# PCB-Schematic-General-Sheet.net
KiCad netlist of a schematic drawn in Altium Designer
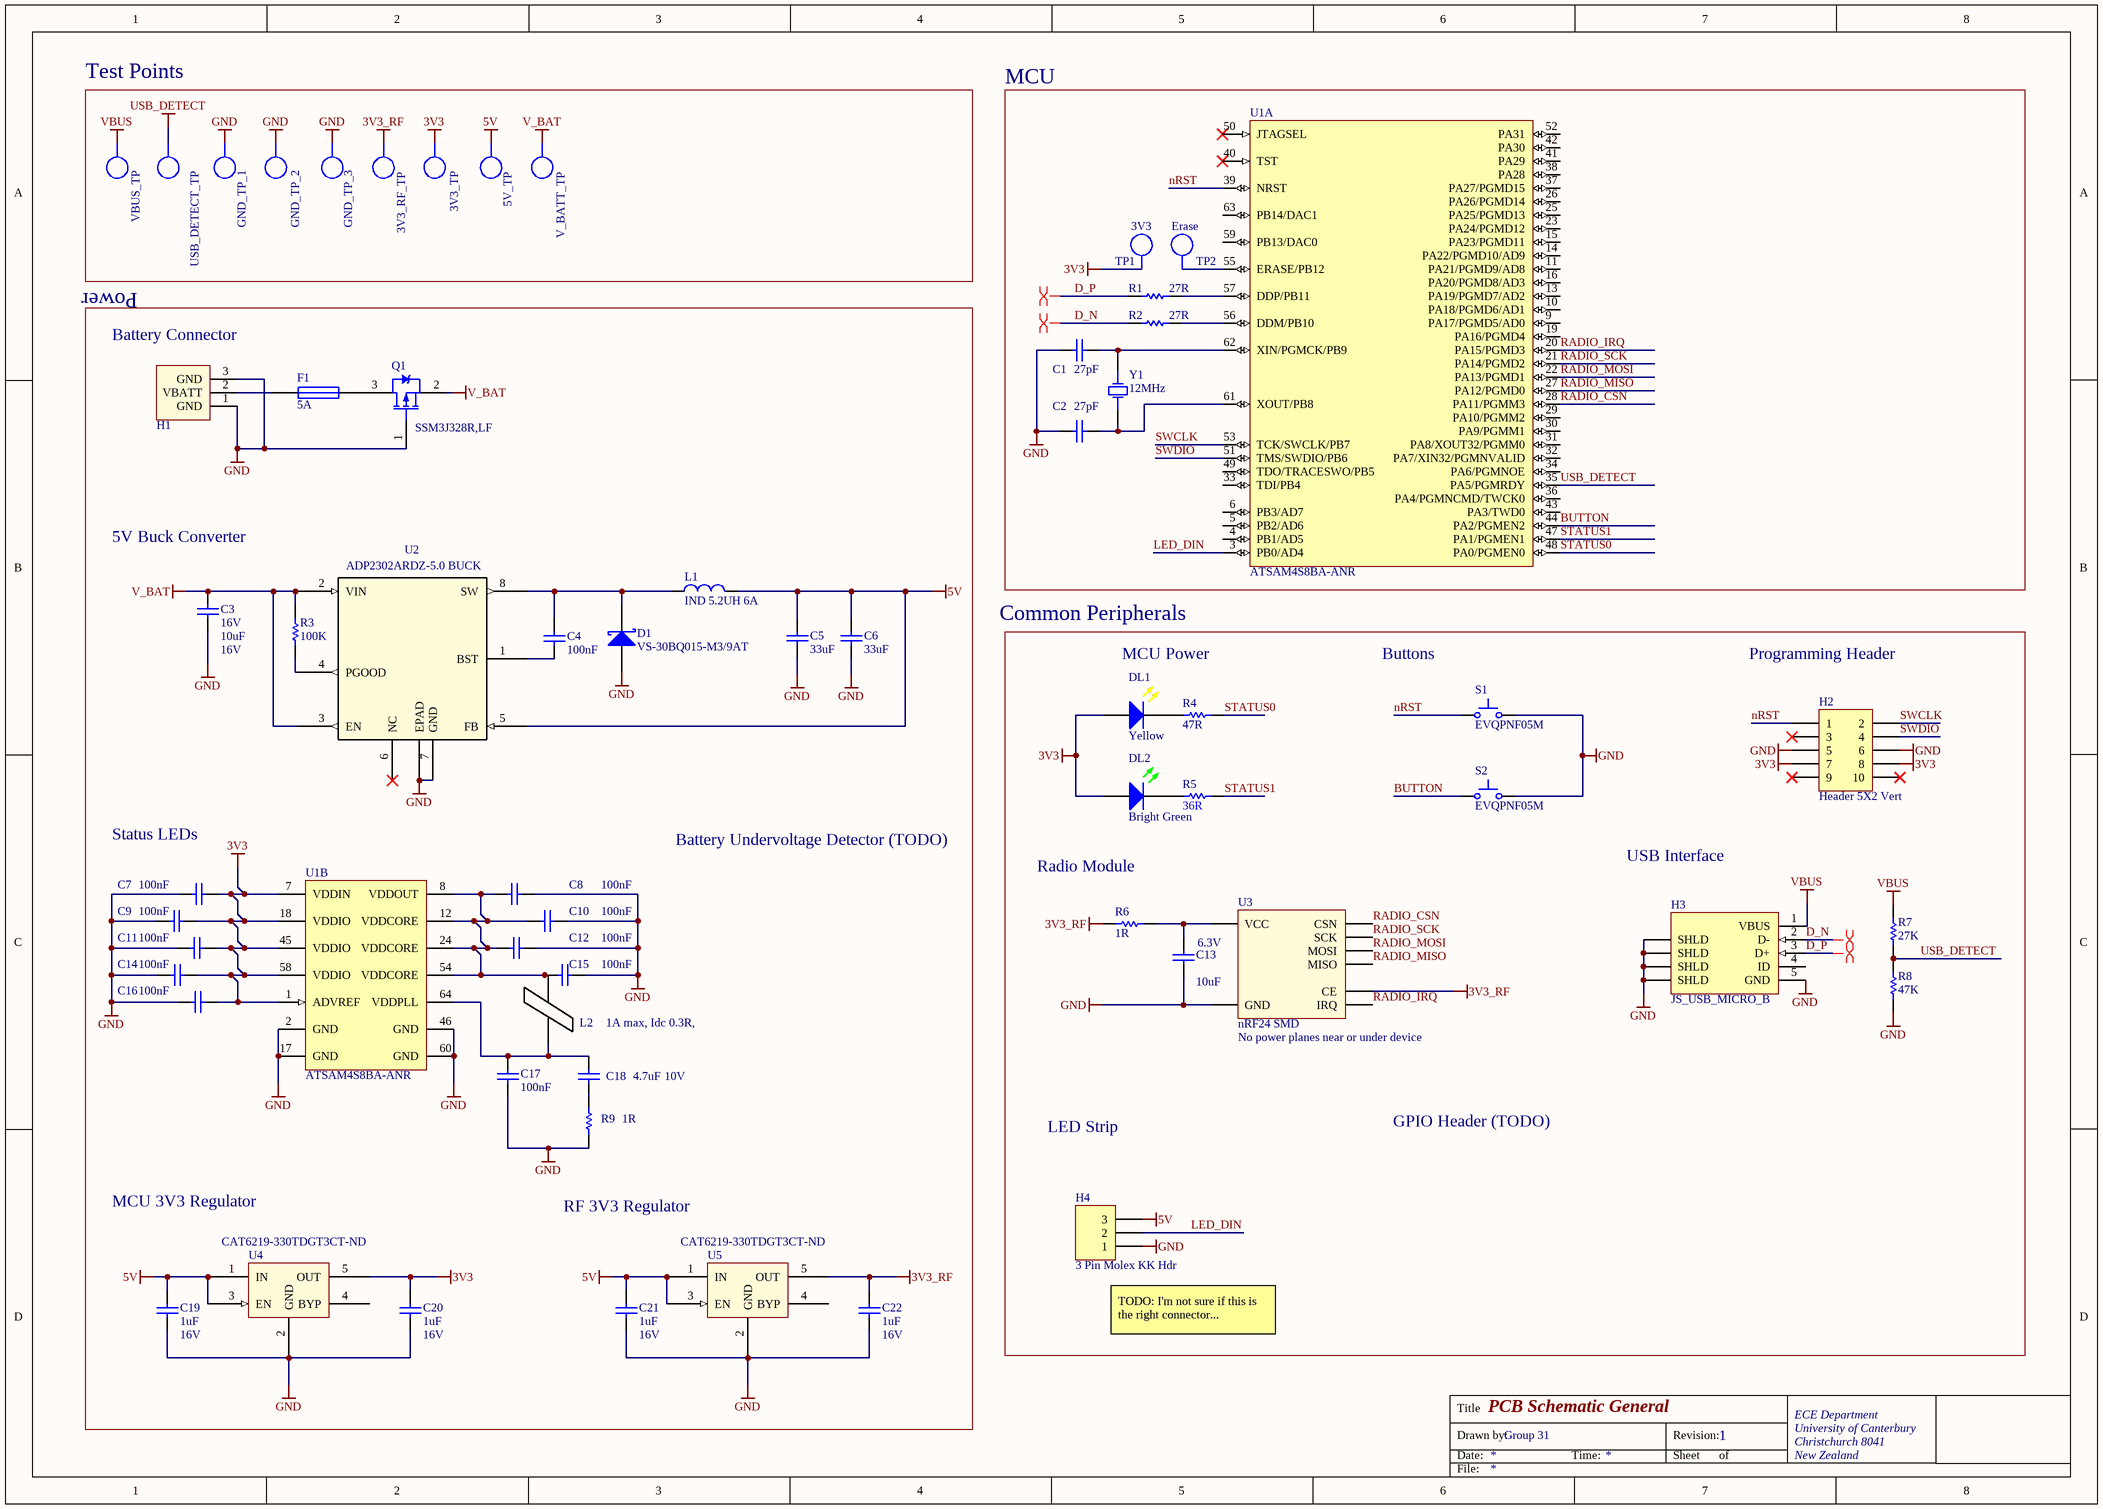
[diagram p0: PCB-Schematic-General-Sheet.schdoc]

(export (version "E")
  (design (tool "Eeschema 10.0.6"))
  (components
    (comp (ref "3V3_RF_TP")
      (value "TP")
      (footprint "TP_1206")
      (description "Test-Point 3.3x1.6x2.1mm SMD")
      (fields
        (field (name "MANUFACTURER") "Harwin Inc")
        (field (name "MANUFACTURER PART NUMBER") "S1751-46R")
      )
      (libsource (lib "ECE AD19Components_19V1") (part "TP_1206"))
    )
    (comp (ref "3V3_TP")
      (value "TP")
      (footprint "TP_1206")
      (description "Test-Point 3.3x1.6x2.1mm SMD")
      (fields
        (field (name "MANUFACTURER") "Harwin Inc")
        (field (name "MANUFACTURER PART NUMBER") "S1751-46R")
      )
      (libsource (lib "ECE AD19Components_19V1") (part "TP_1206"))
    )
    (comp (ref "5V_TP")
      (value "TP")
      (footprint "TP_1206")
      (description "Test-Point 3.3x1.6x2.1mm SMD")
      (fields
        (field (name "MANUFACTURER") "Harwin Inc")
        (field (name "MANUFACTURER PART NUMBER") "S1751-46R")
      )
      (libsource (lib "ECE AD19Components_19V1") (part "TP_1206"))
    )
    (comp (ref "C1")
      (value "27pF")
      (footprint "CAPC1608L")
      (description "CAP CER 27pF NPO/COG +-5% 50V 0603")
      (libsource (lib "ECE AD19Components_19V1") (part "CC_27pF_0603"))
    )
    (comp (ref "C2")
      (value "27pF")
      (footprint "CAPC1608L")
      (description "CAP CER 27pF NPO/COG +-5% 50V 0603")
      (libsource (lib "ECE AD19Components_19V1") (part "CC_27pF_0603"))
    )
    (comp (ref "C3")
      (value "10uF")
      (footprint "CAPC2012L")
      (description "CAP CER 10uF X5R 16V 0805")
      (fields
        (field (name "MANUFACTURER") "Samsung Electro-Mechanics")
        (field (name "MANUFACTURER PART NUMBER") "CL21A106KOQNNWE")
        (field (name "VOLTAGE - RATED") "16V")
        (field (name "MAX VOLTAGE") "16V")
      )
      (libsource (lib "ENCE461AD19_19V2") (part "CC_10uF_16V_0805"))
    )
    (comp (ref "C4")
      (value "100nF")
      (footprint "CAPC1608L")
      (description "CAP CER 100nF X7R +-10% 50V 0603")
      (libsource (lib "ECE AD19Components_19V1") (part "CC_100nF_0603"))
    )
    (comp (ref "C5")
      (value "33uF")
      (footprint "CAPC2012L")
      (description "CAP CER 33uF X5R 6V3 0805")
      (fields
        (field (name "MANUFACTURER") "TDK Corporation")
        (field (name "MANUFACTURER PART NUMBER") "C2012X5R0J336M125AC")
      )
      (libsource (lib "ENCE461AD19_19V2") (part "CC_33uF_6V3_0805"))
    )
    (comp (ref "C6")
      (value "33uF")
      (footprint "CAPC2012L")
      (description "CAP CER 33uF X5R 6V3 0805")
      (fields
        (field (name "MANUFACTURER") "TDK Corporation")
        (field (name "MANUFACTURER PART NUMBER") "C2012X5R0J336M125AC")
      )
      (libsource (lib "ENCE461AD19_19V2") (part "CC_33uF_6V3_0805"))
    )
    (comp (ref "C7")
      (value "100nF")
      (footprint "CAPC1608L")
      (description "CAP CER 100nF X7R +-10% 50V 0603")
      (libsource (lib "ECE AD19Components_19V1") (part "CC_100nF_0603"))
    )
    (comp (ref "C8")
      (value "100nF")
      (footprint "CAPC1608L")
      (description "CAP CER 100nF X7R +-10% 50V 0603")
      (libsource (lib "ECE AD19Components_19V1") (part "CC_100nF_0603"))
    )
    (comp (ref "C9")
      (value "100nF")
      (footprint "CAPC1608L")
      (description "CAP CER 100nF X7R +-10% 50V 0603")
      (libsource (lib "ECE AD19Components_19V1") (part "CC_100nF_0603"))
    )
    (comp (ref "C10")
      (value "100nF")
      (footprint "CAPC1608L")
      (description "CAP CER 100nF X7R +-10% 50V 0603")
      (libsource (lib "ECE AD19Components_19V1") (part "CC_100nF_0603"))
    )
    (comp (ref "C11")
      (value "100nF")
      (footprint "CAPC1608L")
      (description "CAP CER 100nF X7R +-10% 50V 0603")
      (libsource (lib "ECE AD19Components_19V1") (part "CC_100nF_0603"))
    )
    (comp (ref "C12")
      (value "100nF")
      (footprint "CAPC1608L")
      (description "CAP CER 100nF X7R +-10% 50V 0603")
      (libsource (lib "ECE AD19Components_19V1") (part "CC_100nF_0603"))
    )
    (comp (ref "C13")
      (value "10uF")
      (footprint "CAPC1608L")
      (description "CAP CER 10UF X5R +-20% 6V3 0603")
      (fields (field (name "VOLTAGE - RATED") "6.3V"))
      (libsource (lib "ECE AD19Components_19V1") (part "CC_10uF_0603"))
    )
    (comp (ref "C14")
      (value "100nF")
      (footprint "CAPC1608L")
      (description "CAP CER 100nF X7R +-10% 50V 0603")
      (libsource (lib "ECE AD19Components_19V1") (part "CC_100nF_0603"))
    )
    (comp (ref "C15")
      (value "100nF")
      (footprint "CAPC1608L")
      (description "CAP CER 100nF X7R +-10% 50V 0603")
      (libsource (lib "ECE AD19Components_19V1") (part "CC_100nF_0603"))
    )
    (comp (ref "C16")
      (value "100nF")
      (footprint "CAPC1608L")
      (description "CAP CER 100nF X7R +-10% 50V 0603")
      (libsource (lib "ECE AD19Components_19V1") (part "CC_100nF_0603"))
    )
    (comp (ref "C17")
      (value "100nF")
      (footprint "CAPC1608L")
      (description "CAP CER 100nF X7R +-10% 50V 0603")
      (libsource (lib "ECE AD19Components_19V1") (part "CC_100nF_0603"))
    )
    (comp (ref "C18")
      (value "4.7uF")
      (footprint "CAPC1608N")
      (description "CAP CER 4.7uF X5R +-20%  10V 0603")
      (fields (field (name "MAX VOLTAGE") "10V"))
      (libsource (lib "ECE AD19Components_19V1") (part "CC_4.7uF_0603"))
    )
    (comp (ref "C19")
      (value "1uF")
      (footprint "CAPC1608L")
      (description "CAP CER 1uF Y5V -20% +80% 16V 0603")
      (fields (field (name "MAX VOLTAGE") "16V"))
      (libsource (lib "ECE AD19Components_19V1") (part "CC_1uF_0603"))
    )
    (comp (ref "C20")
      (value "1uF")
      (footprint "CAPC1608L")
      (description "CAP CER 1uF Y5V -20% +80% 16V 0603")
      (fields (field (name "MAX VOLTAGE") "16V"))
      (libsource (lib "ECE AD19Components_19V1") (part "CC_1uF_0603"))
    )
    (comp (ref "C21")
      (value "1uF")
      (footprint "CAPC1608L")
      (description "CAP CER 1uF Y5V -20% +80% 16V 0603")
      (fields (field (name "MAX VOLTAGE") "16V"))
      (libsource (lib "ECE AD19Components_19V1") (part "CC_1uF_0603"))
    )
    (comp (ref "C22")
      (value "1uF")
      (footprint "CAPC1608L")
      (description "CAP CER 1uF Y5V -20% +80% 16V 0603")
      (fields (field (name "MAX VOLTAGE") "16V"))
      (libsource (lib "ECE AD19Components_19V1") (part "CC_1uF_0603"))
    )
    (comp (ref "D1")
      (value "VS-30BQ015-M3/9AT")
      (footprint "SMC")
      (description "DIODE, SCHOTTKY, 3A, 15V, DO-214AB / SMC")
      (fields (field (name "MANUFACTURER") "Vishay Semiconductors"))
      (libsource (lib "ECE AD19Components_19V1") (part "DS_VS-30BQ015-M3"))
    )
    (comp (ref "DL1")
      (value "Yellow")
      (footprint "WL-SMCW0603")
      (description "LED Yellow 120mcd 0603 SMD")
      (fields
        (field (name "MANUFACTURER") "WURTH ELEKTRONIK")
        (field (name "MANUFACTURER PART NUMBER") "150060YS75000")
        (field (name "LED COLOUR") "Yellow")
      )
      (libsource (lib "ECE AD19Components_19V1") (part "DL_150060YS75000"))
    )
    (comp (ref "DL2")
      (value "Bright Green")
      (footprint "WL-SMCW0603")
      (description "LED Bright Green 40mcd 0603 SMD")
      (fields
        (field (name "MANUFACTURER") "WURTH ELEKTRONIK")
        (field (name "MANUFACTURER PART NUMBER") "150060VS75000")
        (field (name "LED COLOUR") "Bright Green")
      )
      (libsource (lib "ECE AD19Components_19V1") (part "DL_150060VS75000"))
    )
    (comp (ref "F1")
      (value "5A")
      (footprint "RESC3216N")
      (description "Fuse 5.0A Fast Acting 1206 SMD")
      (fields (field (name "MANUFACTURER PART NUMBER") "C1F5") (field (name "MANUFACTURER") "Bel TRP"))
      (libsource (lib "ECE AD19Components_19V1") (part "FS_Fuse_5.0A"))
    )
    (comp (ref "GND_TP_1")
      (value "TP")
      (footprint "TP_1206")
      (description "Test-Point 3.3x1.6x2.1mm SMD")
      (fields
        (field (name "MANUFACTURER") "Harwin Inc")
        (field (name "MANUFACTURER PART NUMBER") "S1751-46R")
      )
      (libsource (lib "ECE AD19Components_19V1") (part "TP_1206"))
    )
    (comp (ref "GND_TP_2")
      (value "TP")
      (footprint "TP_1206")
      (description "Test-Point 3.3x1.6x2.1mm SMD")
      (fields
        (field (name "MANUFACTURER") "Harwin Inc")
        (field (name "MANUFACTURER PART NUMBER") "S1751-46R")
      )
      (libsource (lib "ECE AD19Components_19V1") (part "TP_1206"))
    )
    (comp (ref "GND_TP_3")
      (value "TP")
      (footprint "TP_1206")
      (description "Test-Point 3.3x1.6x2.1mm SMD")
      (fields
        (field (name "MANUFACTURER") "Harwin Inc")
        (field (name "MANUFACTURER PART NUMBER") "S1751-46R")
      )
      (libsource (lib "ECE AD19Components_19V1") (part "TP_1206"))
    )
    (comp (ref "H1")
      (value "Battery_HEADER_3pin")
      (footprint "BATT_HEADER_3POS")
      (description "3Pin Header 2.54mm spacing")
      (libsource (lib "ENCE461AD19_19V2") (part "Battery_HEADER_3pin"))
    )
    (comp (ref "H2")
      (value "Header 5X2 Vert")
      (footprint "IDC2.54-V10D")
      (description "IDC Header, 2,54mm, 10-Pin, Vert")
      (libsource (lib "ECE AD19Components_19V1") (part "JA_HDR_IDC_5X2_VERT"))
    )
    (comp (ref "H3")
      (value "JS_USB_MICRO_B")
      (footprint "FCI_USB_10118194-0001LF")
      (description "CONN USB MICRO B RECPT SMT R/A")
      (fields (field (name "MANUFACTURER") "FCI") (field (name "MANUFACTURER PART NUMBER") "10118194-0001LF"))
      (libsource (lib "ECE AD19Components_19V1") (part "JS_USB_MICRO_B_SMT"))
    )
    (comp (ref "H4")
      (value "3 Pin Molex KK Hdr")
      (footprint "MOLEX_KK_3_HDR")
      (description "CONN HEADER 3POS 2.54mm VERT_Thru Hole")
      (fields (field (name "MANUFACTURER") "Molex"))
      (libsource (lib "ECE AD19Components_19V1") (part "JA_MOLEX_KK_3POS"))
    )
    (comp (ref "L1")
      (value "IND 5.2UH 6A")
      (footprint "INDUCTOR5u2")
      (description "FIXED IND 5.2UH 6A 22 MOHM SMD")
      (fields
        (field (name "MANUFACTURER") "Sumida America Components Inc.")
        (field (name "MANUFACTURER PART NUMBER") "CDRH104RNP-5R2NC")
      )
      (libsource (lib "ENCE461AD19_19V2") (part "CDRH104RNP-5R2NC"))
    )
    (comp (ref "L2")
      (value "1A max, Idc 0.3R,")
      (footprint "INDC3216L")
      (description "Ferrite Bead, Rdc 0.3R, Z100MHZ 600R, Imax 1A, SMD 1206")
      (fields
        (field (name "MANUFACTURER") "FAIR-RITE")
        (field (name "MANUFACTURER PART NUMBER") "2512066017Y1")
      )
      (libsource (lib "ECE AD19Components_19V1") (part "IN_Ferrite-Bead"))
    )
    (comp (ref "Q1")
      (value "SSM3J328R,LF")
      (footprint "SOT23_L")
      (description "MOSFET P-CH 20V 6A SOT23-3")
      (fields
        (field (name "MANUFACTURER") "Toshiba")
        (field (name "MANUFACTURER PART NUMBER") "SSM3J328R,LF")
      )
      (libsource (lib "ECE AD19Components_19V1") (part "TM_SSM3J328R"))
    )
    (comp (ref "R1")
      (value "27R")
      (footprint "RESC1608L")
      (description "RES 27 OHM 1/10W 5% 0603 SMD")
      (libsource (lib "ECE AD19Components_19V1") (part "RS_27R"))
    )
    (comp (ref "R2")
      (value "27R")
      (footprint "RESC1608L")
      (description "RES 27 OHM 1/10W 5% 0603 SMD")
      (libsource (lib "ECE AD19Components_19V1") (part "RS_27R"))
    )
    (comp (ref "R3")
      (value "100K")
      (footprint "RESC1608L")
      (description "RES 100K OHM 1/10W 5% 0603 SMD")
      (libsource (lib "ECE AD19Components_19V1") (part "RS_100K"))
    )
    (comp (ref "R4")
      (value "47R")
      (footprint "RESC1608L")
      (description "RES 47 OHM 1/10W 5% 0603 SMD")
      (libsource (lib "ECE AD19Components_19V1") (part "RS_47R"))
    )
    (comp (ref "R5")
      (value "36R")
      (footprint "RESC1608L")
      (description "RES 36 OHM 1/10W 5% 0603 SMD")
      (libsource (lib "ECE AD19Components_19V1") (part "RS_36R"))
    )
    (comp (ref "R6")
      (value "1R")
      (footprint "RESC3216L")
      (description "RES 1R OHM 1/4W 5% 1206 SMD")
      (libsource (lib "ECE AD19Components_19V1") (part "RT_1R"))
    )
    (comp (ref "R7")
      (value "27K")
      (footprint "RESC1608L")
      (description "RES 27K OHM 1/10W 5% 0603 SMD")
      (libsource (lib "ECE AD19Components_19V1") (part "RS_27K"))
    )
    (comp (ref "R8")
      (value "47K")
      (footprint "RESC1608N")
      (description "RES 47.0K OHM 1/10W 5% 0603 SMD")
      (libsource (lib "ECE AD19Components_19V1") (part "RS_47K"))
    )
    (comp (ref "R9")
      (value "1R")
      (footprint "RESC3216L")
      (description "RES 1R OHM 1/4W 5% 1206 SMD")
      (libsource (lib "ECE AD19Components_19V1") (part "RT_1R"))
    )
    (comp (ref "S1")
      (value "EVQPNF05M")
      (footprint "EVQPNF05M")
      (description "Panasonic 6 x 3.5mm SMD Light Touch Switch Type SMD")
      (fields (field (name "MANUFACTURER") "Panasonic"))
      (libsource (lib "ECE AD19Components_19V1") (part "WS_EVQPNF05M"))
    )
    (comp (ref "S2")
      (value "EVQPNF05M")
      (footprint "EVQPNF05M")
      (description "Panasonic 6 x 3.5mm SMD Light Touch Switch Type SMD")
      (fields (field (name "MANUFACTURER") "Panasonic"))
      (libsource (lib "ECE AD19Components_19V1") (part "WS_EVQPNF05M"))
    )
    (comp (ref "TP1")
      (value "3V3")
      (footprint "TP_1206")
      (description "Test-Point 3.3x1.6x2.1mm SMD")
      (fields
        (field (name "MANUFACTURER") "Harwin Inc")
        (field (name "MANUFACTURER PART NUMBER") "S1751-46R")
      )
      (libsource (lib "ECE AD19Components_19V1") (part "TP_1206"))
    )
    (comp (ref "TP2")
      (value "Erase")
      (footprint "TP_1206")
      (description "Test-Point 3.3x1.6x2.1mm SMD")
      (fields
        (field (name "MANUFACTURER") "Harwin Inc")
        (field (name "MANUFACTURER PART NUMBER") "S1751-46R")
      )
      (libsource (lib "ECE AD19Components_19V1") (part "TP_1206"))
    )
    (comp (ref "U1")
      (value "ATSAM4S8BA-ANR")
      (footprint "LQFP64_L")
      (description "IC MCU 32BIT 512KB FLASH 64LQFP")
      (fields (field (name "MANUFACTURER") "Atmel"))
      (libsource (lib "ECE AD19Components_19V1") (part "SE_ATSAM4S16BA-MU"))
    )
    (comp (ref "U2")
      (value "ADP2302ARDZ-5.0 BUCK")
      (footprint "RD_8_1")
      (description "IC REG BUCK 5V 2A 8SOIC")
      (fields (field (name "MANUFACTURER_PART_NUMBER") "ADP2302ARDZ-5.0-R7"))
      (libsource (lib "ENCE461AD19_19V2") (part "ADP2302ARDZ-5.0-R7"))
    )
    (comp (ref "U3")
      (value "nRF24 SMD")
      (footprint "NRF24")
      (description "nRF24 SMD Module")
      (fields (field (name "WARNING") "No power planes near or under device"))
      (libsource (lib "ENCE461AD19_19V2") (part "NRF24"))
    )
    (comp (ref "U4")
      (value "CAT6219-330TDGT3")
      (footprint "SOT95P280X145-5N")
      (description "IC REG LIN 3.3V 500MA TSOT23-5")
      (fields
        (field (name "BASE PART NUMBER") "CAT6219")
        (field (name "SUPPLIER PART NUMBER") "CAT6219-330TDGT3CT-ND")
      )
      (libsource (lib "ENCE461AD19_19V2") (part "SV_CAT6219-330TDGT3"))
    )
    (comp (ref "U5")
      (value "CAT6219-330TDGT3")
      (footprint "SOT95P280X145-5N")
      (description "IC REG LIN 3.3V 500MA TSOT23-5")
      (fields
        (field (name "BASE PART NUMBER") "CAT6219")
        (field (name "SUPPLIER PART NUMBER") "CAT6219-330TDGT3CT-ND")
      )
      (libsource (lib "ENCE461AD19_19V2") (part "SV_CAT6219-330TDGT3"))
    )
    (comp (ref "USB_DETECT_TP")
      (value "TP")
      (footprint "TP_1206")
      (description "Test-Point 3.3x1.6x2.1mm SMD")
      (fields
        (field (name "MANUFACTURER") "Harwin Inc")
        (field (name "MANUFACTURER PART NUMBER") "S1751-46R")
      )
      (libsource (lib "ECE AD19Components_19V1") (part "TP_1206"))
    )
    (comp (ref "VBUS_TP")
      (value "TP")
      (footprint "TP_1206")
      (description "Test-Point 3.3x1.6x2.1mm SMD")
      (fields
        (field (name "MANUFACTURER") "Harwin Inc")
        (field (name "MANUFACTURER PART NUMBER") "S1751-46R")
      )
      (libsource (lib "ECE AD19Components_19V1") (part "TP_1206"))
    )
    (comp (ref "V_BATT_TP")
      (value "TP")
      (footprint "TP_1206")
      (description "Test-Point 3.3x1.6x2.1mm SMD")
      (fields
        (field (name "MANUFACTURER") "Harwin Inc")
        (field (name "MANUFACTURER PART NUMBER") "S1751-46R")
      )
      (libsource (lib "ECE AD19Components_19V1") (part "TP_1206"))
    )
    (comp (ref "Y1")
      (value "12MHz")
      (footprint "6.0X3.5-4")
      (description "CRYSTAL 12MHZ 18PF 6X3.5mm SMD")
      (fields
        (field (name "MANUFACTURER") "CTS-Frequency Controls")
        (field (name "MANUFACTURER PART NUMBER") "406C35D12M00000")
        (field (name "FREQUENCY") "12MHz")
      )
      (libsource (lib "ECE AD19Components_19V1") (part "XT_CRYSTAL_12MHz_18pF"))
    )
  )
  (nets
    (net (code "1") (name "/BUTTON") (class "Default")
      (node (ref "S2") (pin "1") (pintype "passive"))
      (node (ref "U1") (pin "44") (pinfunction "PA2/PGMEN2_44") (pintype "bidirectional"))
    )
    (net (code "2") (name "/D_N") (class "Default")
      (node (ref "H3") (pin "2") (pinfunction "D-_2") (pintype "input"))
      (node (ref "R2") (pin "1") (pinfunction "1_1") (pintype "passive"))
    )
    (net (code "3") (name "/D_P") (class "Default")
      (node (ref "H3") (pin "3") (pinfunction "D+_3") (pintype "input"))
      (node (ref "R1") (pin "1") (pinfunction "1_1") (pintype "passive"))
    )
    (net (code "4") (name "/LED_DIN") (class "Default")
      (node (ref "H4") (pin "2") (pinfunction "2_2") (pintype "passive"))
      (node (ref "U1") (pin "3") (pinfunction "PB0/AD4_3") (pintype "bidirectional"))
    )
    (net (code "5") (name "/RADIO_CSN") (class "Default")
      (node (ref "U1") (pin "28") (pinfunction "PA11/PGMM3_28") (pintype "bidirectional"))
      (node (ref "U3") (pin "4") (pinfunction "CSN_4") (pintype "passive"))
    )
    (net (code "6") (name "/RADIO_IRQ") (class "Default")
      (node (ref "U1") (pin "20") (pinfunction "PA15/PGMD3_20") (pintype "bidirectional"))
      (node (ref "U3") (pin "8") (pinfunction "IRQ_8") (pintype "passive"))
    )
    (net (code "7") (name "/RADIO_MISO") (class "Default")
      (node (ref "U1") (pin "27") (pinfunction "PA12/PGMD0_27") (pintype "bidirectional"))
      (node (ref "U3") (pin "7") (pinfunction "MISO_7") (pintype "passive"))
    )
    (net (code "8") (name "/RADIO_MOSI") (class "Default")
      (node (ref "U1") (pin "22") (pinfunction "PA13/PGMD1_22") (pintype "bidirectional"))
      (node (ref "U3") (pin "6") (pinfunction "MOSI_6") (pintype "passive"))
    )
    (net (code "9") (name "/RADIO_SCK") (class "Default")
      (node (ref "U1") (pin "21") (pinfunction "PA14/PGMD2_21") (pintype "bidirectional"))
      (node (ref "U3") (pin "5") (pinfunction "SCK_5") (pintype "passive"))
    )
    (net (code "10") (name "/STATUS0") (class "Default")
      (node (ref "R4") (pin "2") (pinfunction "2_2") (pintype "passive"))
      (node (ref "U1") (pin "48") (pinfunction "PA0/PGMEN0_48") (pintype "bidirectional"))
    )
    (net (code "11") (name "/STATUS1") (class "Default")
      (node (ref "R5") (pin "2") (pinfunction "2_2") (pintype "passive"))
      (node (ref "U1") (pin "47") (pinfunction "PA1/PGMEN1_47") (pintype "bidirectional"))
    )
    (net (code "12") (name "/SWCLK") (class "Default")
      (node (ref "H2") (pin "2") (pinfunction "2_2") (pintype "passive"))
      (node (ref "U1") (pin "53") (pinfunction "TCK/SWCLK/PB7_53") (pintype "bidirectional"))
    )
    (net (code "13") (name "/SWDIO") (class "Default")
      (node (ref "H2") (pin "4") (pinfunction "4_4") (pintype "passive"))
      (node (ref "U1") (pin "51") (pinfunction "TMS/SWDIO/PB6_51") (pintype "bidirectional"))
    )
    (net (code "14") (name "/nRST") (class "Default")
      (node (ref "H2") (pin "1") (pinfunction "1_1") (pintype "passive"))
      (node (ref "S1") (pin "1") (pintype "passive"))
      (node (ref "U1") (pin "39") (pinfunction "NRST_39") (pintype "bidirectional"))
    )
    (net (code "15") (name "3V3") (class "Default")
      (node (ref "3V3_TP") (pin "1") (pinfunction "1_1") (pintype "passive"))
      (node (ref "C11") (pin "2") (pinfunction "2_2") (pintype "passive"))
      (node (ref "C14") (pin "2") (pinfunction "2_2") (pintype "passive"))
      (node (ref "C16") (pin "2") (pinfunction "2_2") (pintype "passive"))
      (node (ref "C20") (pin "2") (pinfunction "2_2") (pintype "passive"))
      (node (ref "C7") (pin "2") (pinfunction "2_2") (pintype "passive"))
      (node (ref "C9") (pin "2") (pinfunction "2_2") (pintype "passive"))
      (node (ref "DL1") (pin "2") (pinfunction "A_2") (pintype "passive"))
      (node (ref "DL2") (pin "2") (pinfunction "A_2") (pintype "passive"))
      (node (ref "H2") (pin "7") (pinfunction "7_7") (pintype "passive"))
      (node (ref "H2") (pin "8") (pinfunction "8_8") (pintype "passive"))
      (node (ref "TP1") (pin "1") (pinfunction "1_1") (pintype "passive"))
      (node (ref "U1") (pin "1") (pinfunction "ADVREF_1") (pintype "input"))
      (node (ref "U1") (pin "18") (pinfunction "VDDIO_18") (pintype "power_in"))
      (node (ref "U1") (pin "45") (pinfunction "VDDIO_45") (pintype "power_in"))
      (node (ref "U1") (pin "58") (pinfunction "VDDIO_58") (pintype "power_in"))
      (node (ref "U1") (pin "7") (pinfunction "VDDIN_7") (pintype "power_in"))
      (node (ref "U4") (pin "5") (pinfunction "OUT_5") (pintype "power_in"))
    )
    (net (code "16") (name "3V3_RF") (class "Default")
      (node (ref "3V3_RF_TP") (pin "1") (pinfunction "1_1") (pintype "passive"))
      (node (ref "C22") (pin "2") (pinfunction "2_2") (pintype "passive"))
      (node (ref "R6") (pin "1") (pinfunction "1_1") (pintype "passive"))
      (node (ref "U3") (pin "3") (pinfunction "CE_3") (pintype "passive"))
      (node (ref "U5") (pin "5") (pinfunction "OUT_5") (pintype "power_in"))
    )
    (net (code "17") (name "5V") (class "Default")
      (node (ref "5V_TP") (pin "1") (pinfunction "1_1") (pintype "passive"))
      (node (ref "C19") (pin "2") (pinfunction "2_2") (pintype "passive"))
      (node (ref "C21") (pin "2") (pinfunction "2_2") (pintype "passive"))
      (node (ref "C5") (pin "2") (pinfunction "2_2") (pintype "passive"))
      (node (ref "C6") (pin "2") (pinfunction "2_2") (pintype "passive"))
      (node (ref "H4") (pin "3") (pinfunction "3_3") (pintype "passive"))
      (node (ref "L1") (pin "2") (pintype "passive"))
      (node (ref "U2") (pin "5") (pinfunction "FB_5") (pintype "input"))
      (node (ref "U4") (pin "1") (pinfunction "IN_1") (pintype "power_in"))
      (node (ref "U4") (pin "3") (pinfunction "EN_3") (pintype "input"))
      (node (ref "U5") (pin "1") (pinfunction "IN_1") (pintype "power_in"))
      (node (ref "U5") (pin "3") (pinfunction "EN_3") (pintype "input"))
    )
    (net (code "18") (name "GND") (class "Default")
      (node (ref "C1") (pin "1") (pinfunction "1_1") (pintype "passive"))
      (node (ref "C10") (pin "2") (pinfunction "2_2") (pintype "passive"))
      (node (ref "C11") (pin "1") (pinfunction "1_1") (pintype "passive"))
      (node (ref "C12") (pin "2") (pinfunction "2_2") (pintype "passive"))
      (node (ref "C13") (pin "1") (pinfunction "1_1") (pintype "passive"))
      (node (ref "C14") (pin "1") (pinfunction "1_1") (pintype "passive"))
      (node (ref "C15") (pin "2") (pinfunction "2_2") (pintype "passive"))
      (node (ref "C16") (pin "1") (pinfunction "1_1") (pintype "passive"))
      (node (ref "C17") (pin "1") (pinfunction "1_1") (pintype "passive"))
      (node (ref "C19") (pin "1") (pinfunction "1_1") (pintype "passive"))
      (node (ref "C2") (pin "1") (pinfunction "1_1") (pintype "passive"))
      (node (ref "C20") (pin "1") (pinfunction "1_1") (pintype "passive"))
      (node (ref "C21") (pin "1") (pinfunction "1_1") (pintype "passive"))
      (node (ref "C22") (pin "1") (pinfunction "1_1") (pintype "passive"))
      (node (ref "C3") (pin "1") (pinfunction "1_1") (pintype "passive"))
      (node (ref "C5") (pin "1") (pinfunction "1_1") (pintype "passive"))
      (node (ref "C6") (pin "1") (pinfunction "1_1") (pintype "passive"))
      (node (ref "C7") (pin "1") (pinfunction "1_1") (pintype "passive"))
      (node (ref "C8") (pin "2") (pinfunction "2_2") (pintype "passive"))
      (node (ref "C9") (pin "1") (pinfunction "1_1") (pintype "passive"))
      (node (ref "D1") (pin "1") (pinfunction "A_1") (pintype "passive"))
      (node (ref "GND_TP_1") (pin "1") (pinfunction "1_1") (pintype "passive"))
      (node (ref "GND_TP_2") (pin "1") (pinfunction "1_1") (pintype "passive"))
      (node (ref "GND_TP_3") (pin "1") (pinfunction "1_1") (pintype "passive"))
      (node (ref "H1") (pin "1") (pinfunction "GND_1") (pintype "passive"))
      (node (ref "H1") (pin "3") (pinfunction "GND_3") (pintype "passive"))
      (node (ref "H2") (pin "5") (pinfunction "5_5") (pintype "passive"))
      (node (ref "H2") (pin "6") (pinfunction "6_6") (pintype "passive"))
      (node (ref "H3") (pin "5") (pinfunction "GND_5") (pintype "passive"))
      (node (ref "H3") (pin "6") (pinfunction "SHLD_6") (pintype "passive"))
      (node (ref "H4") (pin "1") (pinfunction "1_1") (pintype "passive"))
      (node (ref "Q1") (pin "1") (pinfunction "1_1") (pintype "passive"))
      (node (ref "R8") (pin "1") (pinfunction "1_1") (pintype "passive"))
      (node (ref "R9") (pin "1") (pinfunction "1_1") (pintype "passive"))
      (node (ref "S1") (pin "2") (pintype "passive"))
      (node (ref "S2") (pin "2") (pintype "passive"))
      (node (ref "U1") (pin "17") (pinfunction "GND_17") (pintype "power_in"))
      (node (ref "U1") (pin "2") (pinfunction "GND_2") (pintype "power_in"))
      (node (ref "U1") (pin "46") (pinfunction "GND_46") (pintype "power_in"))
      (node (ref "U1") (pin "60") (pinfunction "GND_60") (pintype "power_in"))
      (node (ref "U2") (pin "7") (pinfunction "GND_7") (pintype "power_in"))
      (node (ref "U2") (pin "EPAD") (pinfunction "EPAD_EPAD") (pintype "passive"))
      (node (ref "U3") (pin "2") (pinfunction "GND_2") (pintype "passive"))
      (node (ref "U4") (pin "2") (pinfunction "GND_2") (pintype "power_in"))
      (node (ref "U5") (pin "2") (pinfunction "GND_2") (pintype "power_in"))
    )
    (net (code "19") (name "Net-(C18-Pad1)") (class "Default")
      (node (ref "C18") (pin "1") (pinfunction "1_1") (pintype "passive"))
      (node (ref "R9") (pin "2") (pinfunction "2_2") (pintype "passive"))
    )
    (net (code "20") (name "Net-(D1-K)") (class "Default")
      (node (ref "C4") (pin "2") (pinfunction "2_2") (pintype "passive"))
      (node (ref "D1") (pin "2") (pinfunction "K_2") (pintype "passive"))
      (node (ref "L1") (pin "1") (pintype "passive"))
      (node (ref "U2") (pin "8") (pinfunction "SW_8") (pintype "output"))
    )
    (net (code "21") (name "Net-(DL1-K)") (class "Default")
      (node (ref "DL1") (pin "1") (pinfunction "K_1") (pintype "passive"))
      (node (ref "R4") (pin "1") (pinfunction "1_1") (pintype "passive"))
    )
    (net (code "22") (name "Net-(DL2-K)") (class "Default")
      (node (ref "DL2") (pin "1") (pinfunction "K_1") (pintype "passive"))
      (node (ref "R5") (pin "1") (pinfunction "1_1") (pintype "passive"))
    )
    (net (code "23") (name "Net-(F1-Pad2)") (class "Default")
      (node (ref "F1") (pin "2") (pinfunction "2_2") (pintype "passive"))
      (node (ref "Q1") (pin "3") (pinfunction "3_3") (pintype "passive"))
    )
    (net (code "24") (name "Net-(H1-VBATT)") (class "Default")
      (node (ref "F1") (pin "1") (pinfunction "1_1") (pintype "passive"))
      (node (ref "H1") (pin "2") (pinfunction "VBATT_2") (pintype "passive"))
    )
    (net (code "25") (name "Net-(U1A-DDM{slash}PB10)") (class "Default")
      (node (ref "R2") (pin "2") (pinfunction "2_2") (pintype "passive"))
      (node (ref "U1") (pin "56") (pinfunction "DDM/PB10_56") (pintype "bidirectional"))
    )
    (net (code "26") (name "Net-(U1A-DDP{slash}PB11)") (class "Default")
      (node (ref "R1") (pin "2") (pinfunction "2_2") (pintype "passive"))
      (node (ref "U1") (pin "57") (pinfunction "DDP/PB11_57") (pintype "bidirectional"))
    )
    (net (code "27") (name "Net-(U1A-ERASE{slash}PB12)") (class "Default")
      (node (ref "TP2") (pin "1") (pinfunction "1_1") (pintype "passive"))
      (node (ref "U1") (pin "55") (pinfunction "ERASE/PB12_55") (pintype "bidirectional"))
    )
    (net (code "28") (name "Net-(U1A-XIN{slash}PGMCK{slash}PB9)") (class "Default")
      (node (ref "C1") (pin "2") (pinfunction "2_2") (pintype "passive"))
      (node (ref "U1") (pin "62") (pinfunction "XIN/PGMCK/PB9_62") (pintype "bidirectional"))
      (node (ref "Y1") (pin "1") (pinfunction "OSC1_1") (pintype "passive"))
    )
    (net (code "29") (name "Net-(U1A-XOUT{slash}PB8)") (class "Default")
      (node (ref "C2") (pin "2") (pinfunction "2_2") (pintype "passive"))
      (node (ref "U1") (pin "61") (pinfunction "XOUT/PB8_61") (pintype "bidirectional"))
      (node (ref "Y1") (pin "3") (pinfunction "OSC2_3") (pintype "passive"))
    )
    (net (code "30") (name "Net-(U1B-VDDOUT)") (class "Default")
      (node (ref "C10") (pin "1") (pinfunction "1_1") (pintype "passive"))
      (node (ref "C12") (pin "1") (pinfunction "1_1") (pintype "passive"))
      (node (ref "C15") (pin "1") (pinfunction "1_1") (pintype "passive"))
      (node (ref "C8") (pin "1") (pinfunction "1_1") (pintype "passive"))
      (node (ref "L2") (pin "2") (pinfunction "2_2") (pintype "passive"))
      (node (ref "U1") (pin "12") (pinfunction "VDDCORE_12") (pintype "power_in"))
      (node (ref "U1") (pin "24") (pinfunction "VDDCORE_24") (pintype "power_in"))
      (node (ref "U1") (pin "54") (pinfunction "VDDCORE_54") (pintype "power_in"))
      (node (ref "U1") (pin "8") (pinfunction "VDDOUT_8") (pintype "power_in"))
    )
    (net (code "31") (name "Net-(U1B-VDDPLL)") (class "Default")
      (node (ref "C17") (pin "2") (pinfunction "2_2") (pintype "passive"))
      (node (ref "C18") (pin "2") (pinfunction "2_2") (pintype "passive"))
      (node (ref "L2") (pin "1") (pinfunction "1_1") (pintype "passive"))
      (node (ref "U1") (pin "64") (pinfunction "VDDPLL_64") (pintype "power_in"))
    )
    (net (code "32") (name "Net-(U2-BST)") (class "Default")
      (node (ref "C4") (pin "1") (pinfunction "1_1") (pintype "passive"))
      (node (ref "U2") (pin "1") (pinfunction "BST_1") (pintype "passive"))
    )
    (net (code "33") (name "Net-(U2-PGOOD)") (class "Default")
      (node (ref "R3") (pin "1") (pinfunction "1_1") (pintype "passive"))
      (node (ref "U2") (pin "4") (pinfunction "PGOOD_4") (pintype "output"))
    )
    (net (code "34") (name "Net-(U3-VCC)") (class "Default")
      (node (ref "C13") (pin "2") (pinfunction "2_2") (pintype "passive"))
      (node (ref "R6") (pin "2") (pinfunction "2_2") (pintype "passive"))
      (node (ref "U3") (pin "1") (pinfunction "VCC_1") (pintype "passive"))
    )
    (net (code "35") (name "USB_DETECT") (class "Default")
      (node (ref "R7") (pin "1") (pinfunction "1_1") (pintype "passive"))
      (node (ref "R8") (pin "2") (pinfunction "2_2") (pintype "passive"))
      (node (ref "U1") (pin "35") (pinfunction "PA5/PGMRDY_35") (pintype "bidirectional"))
      (node (ref "USB_DETECT_TP") (pin "1") (pinfunction "1_1") (pintype "passive"))
    )
    (net (code "36") (name "VBUS") (class "Default")
      (node (ref "H3") (pin "1") (pinfunction "VBUS_1") (pintype "power_in"))
      (node (ref "R7") (pin "2") (pinfunction "2_2") (pintype "passive"))
      (node (ref "VBUS_TP") (pin "1") (pinfunction "1_1") (pintype "passive"))
    )
    (net (code "37") (name "V_BAT") (class "Default")
      (node (ref "C3") (pin "2") (pinfunction "2_2") (pintype "passive"))
      (node (ref "Q1") (pin "2") (pinfunction "2_2") (pintype "passive"))
      (node (ref "R3") (pin "2") (pinfunction "2_2") (pintype "passive"))
      (node (ref "U2") (pin "2") (pinfunction "VIN_2") (pintype "input"))
      (node (ref "U2") (pin "3") (pinfunction "EN_3") (pintype "output"))
      (node (ref "V_BATT_TP") (pin "1") (pinfunction "1_1") (pintype "passive"))
    )
    (net (code "38") (name "unconnected-(H2-Pad3)") (class "Default")
      (node (ref "H2") (pin "3") (pinfunction "3_3") (pintype "passive+no_connect"))
    )
    (net (code "39") (name "unconnected-(H2-Pad9)") (class "Default")
      (node (ref "H2") (pin "9") (pinfunction "9_9") (pintype "passive+no_connect"))
    )
    (net (code "40") (name "unconnected-(H2-Pad10)") (class "Default")
      (node (ref "H2") (pin "10") (pinfunction "10_10") (pintype "passive+no_connect"))
    )
    (net (code "41") (name "unconnected-(H3-ID-Pad4)") (class "Default")
      (node (ref "H3") (pin "4") (pinfunction "ID_4") (pintype "power_in"))
    )
    (net (code "42") (name "unconnected-(U1A-JTAGSEL-Pad50)") (class "Default")
      (node (ref "U1") (pin "50") (pinfunction "JTAGSEL_50") (pintype "input+no_connect"))
    )
    (net (code "43") (name "unconnected-(U1A-PA3{slash}TWD0-Pad43)") (class "Default")
      (node (ref "U1") (pin "43") (pinfunction "PA3/TWD0_43") (pintype "bidirectional"))
    )
    (net (code "44") (name "unconnected-(U1A-PA4{slash}PGMNCMD{slash}TWCK0-Pad36)") (class "Default")
      (node (ref "U1") (pin "36") (pinfunction "PA4/PGMNCMD/TWCK0_36") (pintype "bidirectional"))
    )
    (net (code "45") (name "unconnected-(U1A-PA6{slash}PGMNOE-Pad34)") (class "Default")
      (node (ref "U1") (pin "34") (pinfunction "PA6/PGMNOE_34") (pintype "bidirectional"))
    )
    (net (code "46") (name "unconnected-(U1A-PA7{slash}XIN32{slash}PGMNVALID-Pad32)") (class "Default")
      (node (ref "U1") (pin "32") (pinfunction "PA7/XIN32/PGMNVALID_32") (pintype "bidirectional"))
    )
    (net (code "47") (name "unconnected-(U1A-PA8{slash}XOUT32{slash}PGMM0-Pad31)") (class "Default")
      (node (ref "U1") (pin "31") (pinfunction "PA8/XOUT32/PGMM0_31") (pintype "bidirectional"))
    )
    (net (code "48") (name "unconnected-(U1A-PA9{slash}PGMM1-Pad30)") (class "Default")
      (node (ref "U1") (pin "30") (pinfunction "PA9/PGMM1_30") (pintype "bidirectional"))
    )
    (net (code "49") (name "unconnected-(U1A-PA10{slash}PGMM2-Pad29)") (class "Default")
      (node (ref "U1") (pin "29") (pinfunction "PA10/PGMM2_29") (pintype "bidirectional"))
    )
    (net (code "50") (name "unconnected-(U1A-PA16{slash}PGMD4-Pad19)") (class "Default")
      (node (ref "U1") (pin "19") (pinfunction "PA16/PGMD4_19") (pintype "bidirectional"))
    )
    (net (code "51") (name "unconnected-(U1A-PA17{slash}PGMD5{slash}AD0-Pad9)") (class "Default")
      (node (ref "U1") (pin "9") (pinfunction "PA17/PGMD5/AD0_9") (pintype "bidirectional"))
    )
    (net (code "52") (name "unconnected-(U1A-PA18{slash}PGMD6{slash}AD1-Pad10)") (class "Default")
      (node (ref "U1") (pin "10") (pinfunction "PA18/PGMD6/AD1_10") (pintype "bidirectional"))
    )
    (net (code "53") (name "unconnected-(U1A-PA19{slash}PGMD7{slash}AD2-Pad13)") (class "Default")
      (node (ref "U1") (pin "13") (pinfunction "PA19/PGMD7/AD2_13") (pintype "bidirectional"))
    )
    (net (code "54") (name "unconnected-(U1A-PA20{slash}PGMD8{slash}AD3-Pad16)") (class "Default")
      (node (ref "U1") (pin "16") (pinfunction "PA20/PGMD8/AD3_16") (pintype "bidirectional"))
    )
    (net (code "55") (name "unconnected-(U1A-PA21{slash}PGMD9{slash}AD8-Pad11)") (class "Default")
      (node (ref "U1") (pin "11") (pinfunction "PA21/PGMD9/AD8_11") (pintype "bidirectional"))
    )
    (net (code "56") (name "unconnected-(U1A-PA22{slash}PGMD10{slash}AD9-Pad14)") (class "Default")
      (node (ref "U1") (pin "14") (pinfunction "PA22/PGMD10/AD9_14") (pintype "bidirectional"))
    )
    (net (code "57") (name "unconnected-(U1A-PA23{slash}PGMD11-Pad15)") (class "Default")
      (node (ref "U1") (pin "15") (pinfunction "PA23/PGMD11_15") (pintype "bidirectional"))
    )
    (net (code "58") (name "unconnected-(U1A-PA24{slash}PGMD12-Pad23)") (class "Default")
      (node (ref "U1") (pin "23") (pinfunction "PA24/PGMD12_23") (pintype "bidirectional"))
    )
    (net (code "59") (name "unconnected-(U1A-PA25{slash}PGMD13-Pad25)") (class "Default")
      (node (ref "U1") (pin "25") (pinfunction "PA25/PGMD13_25") (pintype "bidirectional"))
    )
    (net (code "60") (name "unconnected-(U1A-PA26{slash}PGMD14-Pad26)") (class "Default")
      (node (ref "U1") (pin "26") (pinfunction "PA26/PGMD14_26") (pintype "bidirectional"))
    )
    (net (code "61") (name "unconnected-(U1A-PA27{slash}PGMD15-Pad37)") (class "Default")
      (node (ref "U1") (pin "37") (pinfunction "PA27/PGMD15_37") (pintype "bidirectional"))
    )
    (net (code "62") (name "unconnected-(U1A-PA28-Pad38)") (class "Default")
      (node (ref "U1") (pin "38") (pinfunction "PA28_38") (pintype "bidirectional"))
    )
    (net (code "63") (name "unconnected-(U1A-PA29-Pad41)") (class "Default")
      (node (ref "U1") (pin "41") (pinfunction "PA29_41") (pintype "bidirectional"))
    )
    (net (code "64") (name "unconnected-(U1A-PA30-Pad42)") (class "Default")
      (node (ref "U1") (pin "42") (pinfunction "PA30_42") (pintype "bidirectional"))
    )
    (net (code "65") (name "unconnected-(U1A-PA31-Pad52)") (class "Default")
      (node (ref "U1") (pin "52") (pinfunction "PA31_52") (pintype "bidirectional"))
    )
    (net (code "66") (name "unconnected-(U1A-PB1{slash}AD5-Pad4)") (class "Default")
      (node (ref "U1") (pin "4") (pinfunction "PB1/AD5_4") (pintype "bidirectional"))
    )
    (net (code "67") (name "unconnected-(U1A-PB2{slash}AD6-Pad5)") (class "Default")
      (node (ref "U1") (pin "5") (pinfunction "PB2/AD6_5") (pintype "bidirectional"))
    )
    (net (code "68") (name "unconnected-(U1A-PB3{slash}AD7-Pad6)") (class "Default")
      (node (ref "U1") (pin "6") (pinfunction "PB3/AD7_6") (pintype "bidirectional"))
    )
    (net (code "69") (name "unconnected-(U1A-PB13{slash}DAC0-Pad59)") (class "Default")
      (node (ref "U1") (pin "59") (pinfunction "PB13/DAC0_59") (pintype "bidirectional"))
    )
    (net (code "70") (name "unconnected-(U1A-PB14{slash}DAC1-Pad63)") (class "Default")
      (node (ref "U1") (pin "63") (pinfunction "PB14/DAC1_63") (pintype "bidirectional"))
    )
    (net (code "71") (name "unconnected-(U1A-TDI{slash}PB4-Pad33)") (class "Default")
      (node (ref "U1") (pin "33") (pinfunction "TDI/PB4_33") (pintype "bidirectional"))
    )
    (net (code "72") (name "unconnected-(U1A-TDO{slash}TRACESWO{slash}PB5-Pad49)") (class "Default")
      (node (ref "U1") (pin "49") (pinfunction "TDO/TRACESWO/PB5_49") (pintype "bidirectional"))
    )
    (net (code "73") (name "unconnected-(U1A-TST-Pad40)") (class "Default")
      (node (ref "U1") (pin "40") (pinfunction "TST_40") (pintype "input+no_connect"))
    )
    (net (code "74") (name "unconnected-(U2-NC-Pad6)") (class "Default")
      (node (ref "U2") (pin "6") (pinfunction "NC_6") (pintype "passive+no_connect"))
    )
    (net (code "75") (name "unconnected-(U4-BYP-Pad4)") (class "Default")
      (node (ref "U4") (pin "4") (pinfunction "BYP_4") (pintype "passive"))
    )
    (net (code "76") (name "unconnected-(U5-BYP-Pad4)") (class "Default")
      (node (ref "U5") (pin "4") (pinfunction "BYP_4") (pintype "passive"))
    )
  )
)
